# Hoja_principal_Sumo_2024.net
KiCad netlist of a schematic drawn in Altium Designer
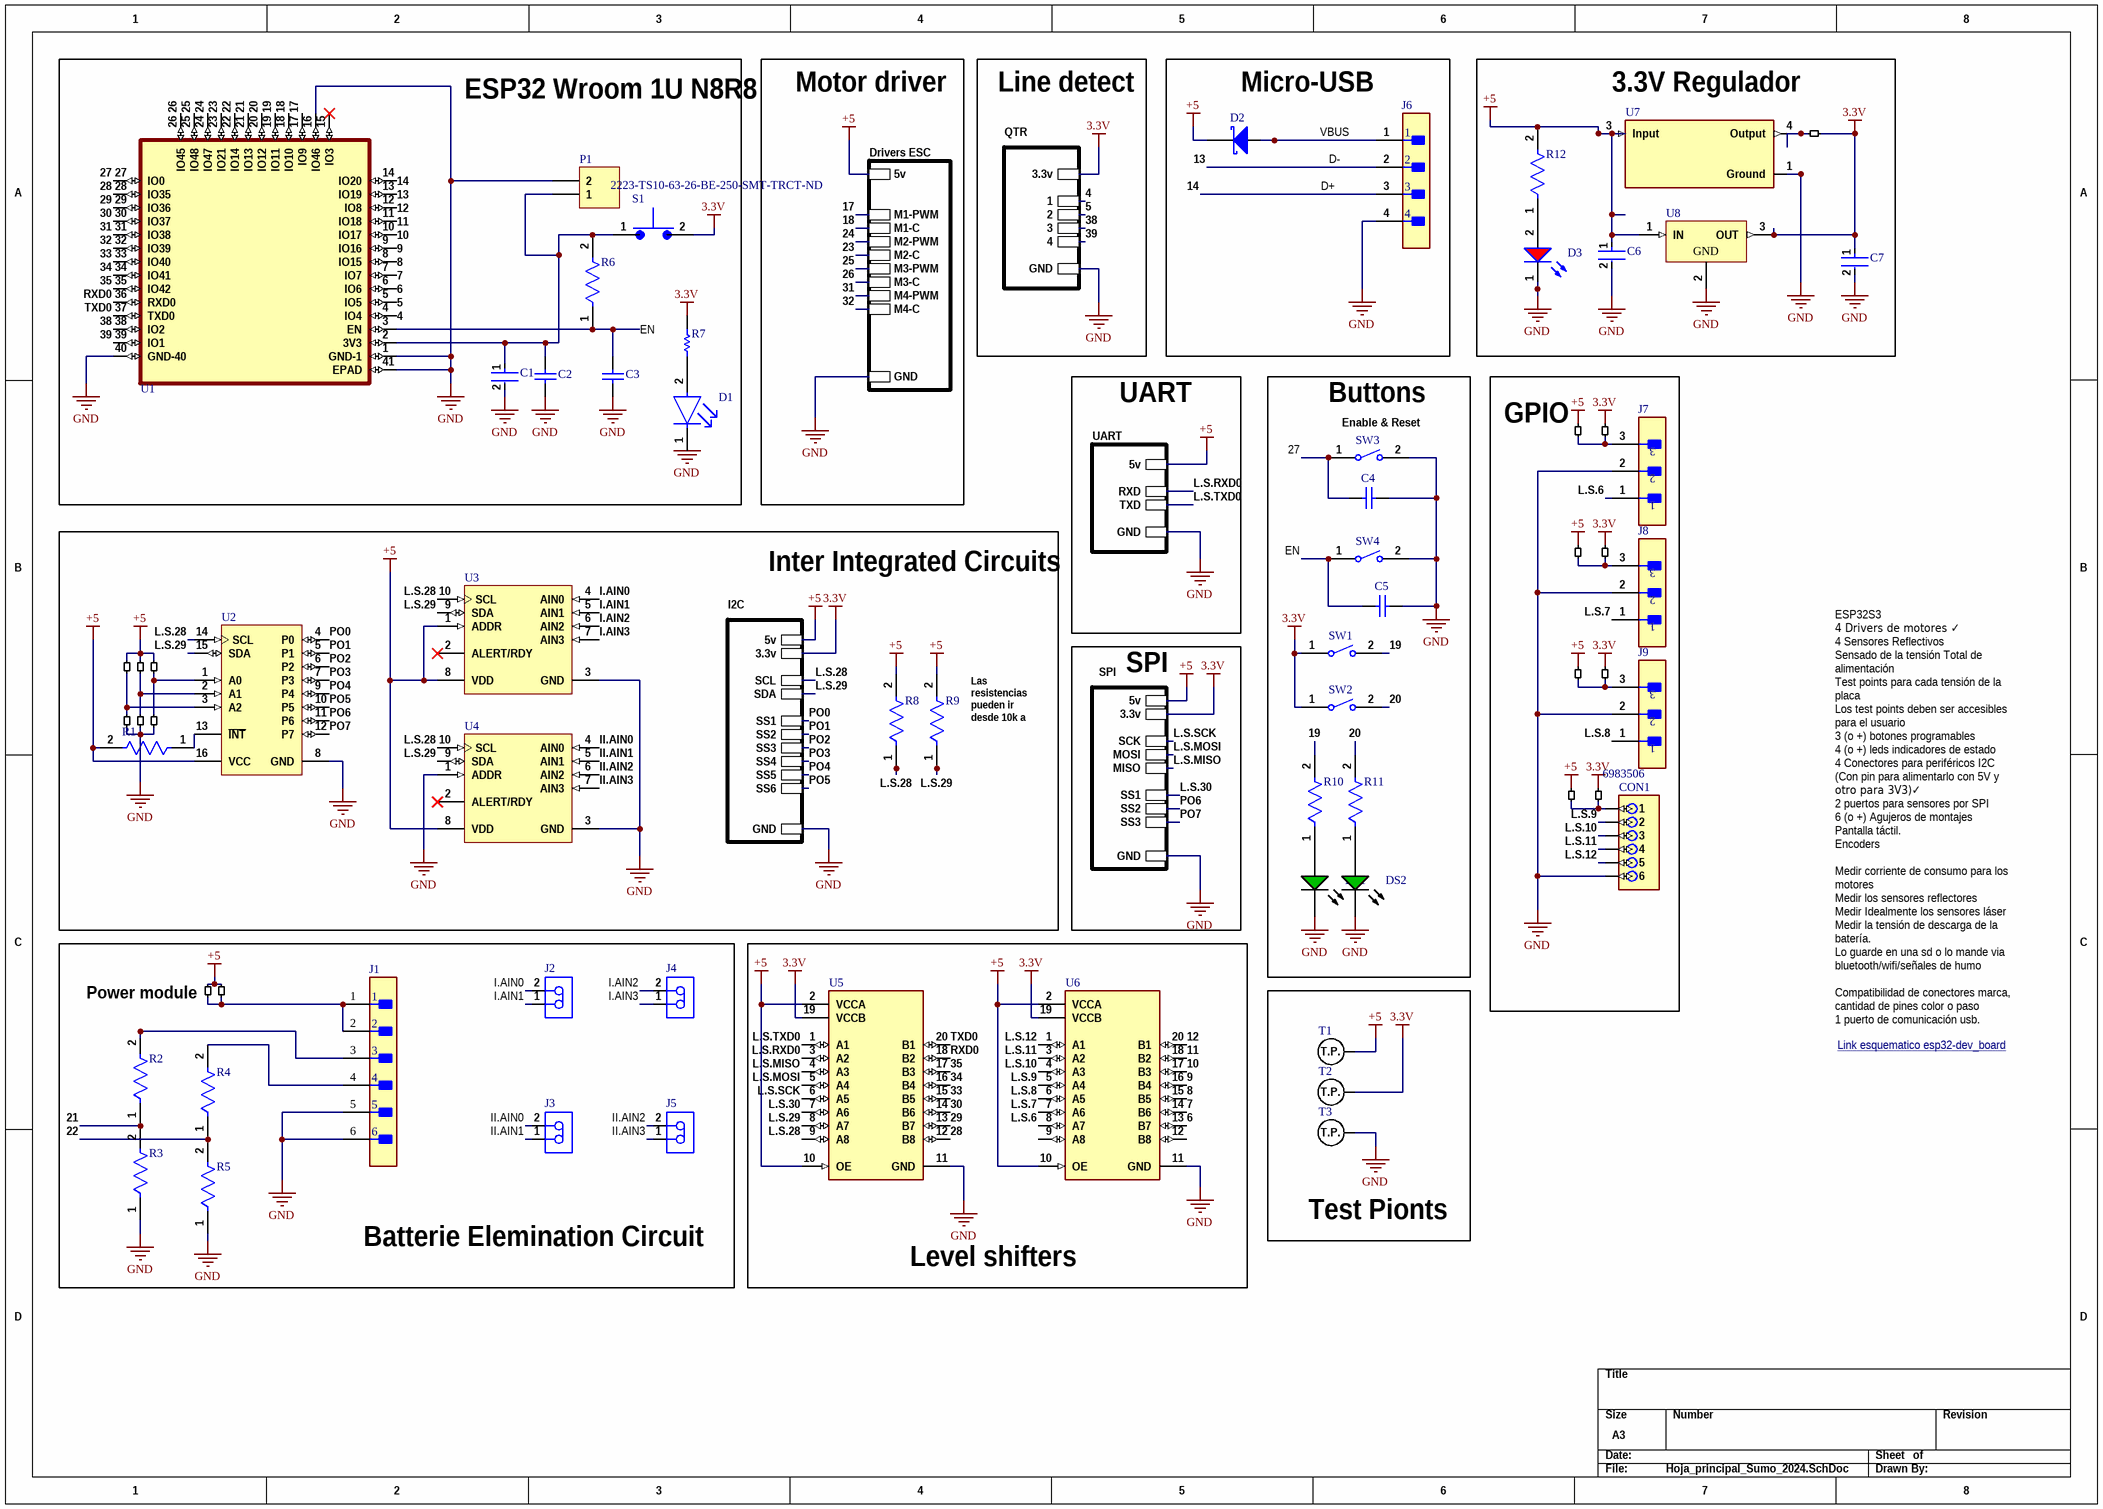
[diagram p0: Hoja_principal_Sumo_2024.SchDoc]

(export (version "E")
  (design (tool "Eeschema 10.0.6"))
  (components
    (comp (ref "C1")
      (value "TMK212BBJ106KG-T")
      (footprint "FP-0805-L_2_0_0_2-W_1_25-MFG")
      (description "Multilayer Ceramic Capacitor 10uF 25V X5R 10% SMD 0805 T/R")
      (fields (field (name "VOLTAGE") "16V") (field (name "TOLERANCE") "10%"))
      (libsource (lib "Altium Content Vault") (part "02cd4be3c70576c341d710602a673aa"))
    )
    (comp (ref "C2")
      (value "GRM21BR71H104KA01L")
      (footprint "CAPC2013X135X45ML10T25")
      (description "Chip Capacitor, 0.1 uF, +/- 10%, 50 V, -55 to 125 degC, 0805 (2012 Metric), RoHS, Tape and Reel")
      (fields (field (name "VOLTAGE") "50V") (field (name "TOLERANCE") "10%"))
      (libsource (lib "Altium Content Vault") (part "CAP-NP-2"))
    )
    (comp (ref "C3")
      (value "C0805C105K4PACTU")
      (footprint "CAPC2013X145X50LL20T25")
      (fields (field (name "MANUFACTURER") "Kemet"))
      (libsource (lib "Altium Content Vault") (part "CAP"))
    )
    (comp (ref "C4")
      (value "GRM21BR71H104KA01L")
      (footprint "CAPC2013X135X45ML10T25")
      (description "Chip Capacitor, 0.1 uF, +/- 10%, 50 V, -55 to 125 degC, 0805 (2012 Metric), RoHS, Tape and Reel")
      (fields (field (name "VOLTAGE") "50V") (field (name "TOLERANCE") "10%"))
      (libsource (lib "Altium Content Vault") (part "CAP-NP-2"))
    )
    (comp (ref "C5")
      (value "GRM21BR71H104KA01L")
      (footprint "CAPC2013X135X45ML10T25")
      (description "Chip Capacitor, 0.1 uF, +/- 10%, 50 V, -55 to 125 degC, 0805 (2012 Metric), RoHS, Tape and Reel")
      (fields (field (name "VOLTAGE") "50V") (field (name "TOLERANCE") "10%"))
      (libsource (lib "Altium Content Vault") (part "CAP-NP-2"))
    )
    (comp (ref "C6")
      (value "GRM31CR71A226KE15L")
      (footprint "FP-GRM31C-0_2-e0_3_0_8-MFG")
      (description "Chip Multilayer Ceramic Capacitors for General Purpose, 1206, 22uF, X7R, 15%, 10%, 10V")
      (fields (field (name "VOLTAGE") "10V") (field (name "TOLERANCE") "10%"))
      (libsource (lib "Altium Content Vault") (part "02cd4be3c70576c341d710602a673aa"))
    )
    (comp (ref "C7")
      (value "GRM31CR71A226KE15L")
      (footprint "FP-GRM31C-0_2-e0_3_0_8-MFG")
      (description "Chip Multilayer Ceramic Capacitors for General Purpose, 1206, 22uF, X7R, 15%, 10%, 10V")
      (fields (field (name "VOLTAGE") "10V") (field (name "TOLERANCE") "10%"))
      (libsource (lib "Altium Content Vault") (part "02cd4be3c70576c341d710602a673aa"))
    )
    (comp (ref "CON1")
      (value "B6B-ZR")
      (footprint "B6B-ZR")
      (description "Connector Header Surface Mount 6 position 0.059 (1.50mm)")
      (fields (field (name "MF") "JST") (field (name "SUPPLIER PART NUMBER 1") "6983506"))
      (libsource (lib "B6B-ZR") (part "B6B-ZR"))
    )
    (comp (ref "D1")
      (value "APHCM2012SYCK-F01")
      (footprint "FP-APHCM2012SYCK-F01-MFG")
      (description "LED YELLOW CLEAR CHIP SMD")
      (libsource (lib "Altium Content Vault") (part "8706943c75ba83719d021d2fdc84c58"))
    )
    (comp (ref "D2")
      (value "BAS3010A03WE6327HTSA1")
      (footprint "INF-SOD323_V")
      (description "Medium Power AF Schottky Diode, 0.41 V, 1 A, -65 to 125 degC, 2-Pin SOD323, RoHS, Tape and Reel")
      (fields (field (name "MANUFACTURER") "Infineon"))
      (libsource (lib "Altium Content Vault") (part "DSKY-KA-2"))
    )
    (comp (ref "D3")
      (value "150080SS75000")
      (footprint "WL-SMCW_0805_150080xx75000")
      (libsource (lib "Altium Content Vault") (part "LED_Red_2A-1K"))
    )
    (comp (ref "DS1")
      (value "HSMG-C170")
      (footprint "AVAG-HSMX-C170_V")
      (description "Chip LED, Green, 2.2 V, -40 to 85 degC, 2-Pin SMD, Pb-Free, Tape and Reel")
      (fields (field (name "MANUFACTURER") "Avago"))
      (libsource (lib "Altium Content Vault") (part "LED_GREEN_A1K2-2"))
    )
    (comp (ref "DS2")
      (value "HSMG-C170")
      (footprint "AVAG-HSMX-C170_V")
      (description "Chip LED, Green, 2.2 V, -40 to 85 degC, 2-Pin SMD, Pb-Free, Tape and Reel")
      (fields (field (name "MANUFACTURER") "Avago"))
      (libsource (lib "Altium Content Vault") (part "LED_GREEN_A1K2-2"))
    )
    (comp (ref "J1")
      (value "B6B-PH-K-K(LF)(SN)")
      (footprint "FP-B6B-PH-K-K_LF_SN-MFG")
      (description "PH Series 6 Position 2 mm Pitch Through Hole Top Entry Shrouded Header")
      (libsource (lib "Altium Content Vault") (part "f2cb566baf1c37ab5a3b8e90bbeafd6"))
    )
    (comp (ref "J2")
      (value "B2B-PH-K-S(LF)(SN)")
      (footprint "JST-B2B-PH-K-S_V")
      (fields (field (name "MANUFACTURER") "JST"))
      (libsource (lib "Altium Content Vault") (part "CN-2P-F-QF2"))
    )
    (comp (ref "J3")
      (value "B2B-PH-K-S(LF)(SN)")
      (footprint "JST-B2B-PH-K-S_V")
      (fields (field (name "MANUFACTURER") "JST"))
      (libsource (lib "Altium Content Vault") (part "CN-2P-F-QF2"))
    )
    (comp (ref "J4")
      (value "B2B-PH-K-S(LF)(SN)")
      (footprint "JST-B2B-PH-K-S_V")
      (fields (field (name "MANUFACTURER") "JST"))
      (libsource (lib "Altium Content Vault") (part "CN-2P-F-QF2"))
    )
    (comp (ref "J5")
      (value "B2B-PH-K-S(LF)(SN)")
      (footprint "JST-B2B-PH-K-S_V")
      (fields (field (name "MANUFACTURER") "JST"))
      (libsource (lib "Altium Content Vault") (part "CN-2P-F-QF2"))
    )
    (comp (ref "J6")
      (value "B4B-ZR(LF)(SN)")
      (footprint "FP-B4B-ZR_LF_SN-MFG")
      (description "CONN HEADER VERT 4POS 1.5MM")
      (libsource (lib "Altium Content Vault") (part "299a8cea1bdcbc3624fe62c390fa72c"))
    )
    (comp (ref "J7")
      (value "B3B-ZR(LF)(SN)")
      (footprint "FP-B3B-ZR_LF_SN-MFG")
      (description "CONN HEADER VERT 3POS 1.5MM")
      (libsource (lib "Altium Content Vault") (part "0d3f023dd272f625e17a2be33dea85f"))
    )
    (comp (ref "J8")
      (value "B3B-ZR(LF)(SN)")
      (footprint "FP-B3B-ZR_LF_SN-MFG")
      (description "CONN HEADER VERT 3POS 1.5MM")
      (libsource (lib "Altium Content Vault") (part "0d3f023dd272f625e17a2be33dea85f"))
    )
    (comp (ref "J9")
      (value "B3B-ZR(LF)(SN)")
      (footprint "FP-B3B-ZR_LF_SN-MFG")
      (description "CONN HEADER VERT 3POS 1.5MM")
      (libsource (lib "Altium Content Vault") (part "0d3f023dd272f625e17a2be33dea85f"))
    )
    (comp (ref "P1")
      (value "Header 2")
      (footprint "HDR1X2")
      (description "Header, 2-Pin")
      (fields (field (name "PUBLISHER") "Altium Limited"))
      (libsource (lib "Miscellaneous Connectors") (part "Header 2"))
    )
    (comp (ref "R1")
      (value "CRCW080510K0FKEA")
      (footprint "FP-CRCW0805-e3-IPC_A")
      (description "RES Thick Film, 10kΩ, 1%, 0.125W, 100ppm/°C, 0805")
      (fields (field (name "TOLERANCE") "1%"))
      (libsource (lib "Altium Content Vault") (part "1029c3af85768c4190bb7ad29bc67b5"))
    )
    (comp (ref "R2")
      (value "RC0805FR-07100KL")
      (footprint "FP-RC0805-0_6-IPC_C")
      (description "RES 100K OHM 1% 1/8W 0805")
      (fields (field (name "TOLERANCE") "1%"))
      (libsource (lib "Altium Content Vault") (part "1029c3af85768c4190bb7ad29bc67b5"))
    )
    (comp (ref "R3")
      (value "CRCW080547K0FKEA")
      (footprint "FP-CRCW0805-e3-MFG")
      (description "RES Thick Film, 47kΩ, 1%, 0.125W, 100ppm/°C, 0805")
      (fields (field (name "TOLERANCE") "1%"))
      (libsource (lib "Altium Content Vault") (part "1029c3af85768c4190bb7ad29bc67b5"))
    )
    (comp (ref "R4")
      (value "RC0805FR-07100KL")
      (footprint "FP-RC0805-0_6-IPC_C")
      (description "RES 100K OHM 1% 1/8W 0805")
      (fields (field (name "TOLERANCE") "1%"))
      (libsource (lib "Altium Content Vault") (part "1029c3af85768c4190bb7ad29bc67b5"))
    )
    (comp (ref "R5")
      (value "CRCW080547K0FKEA")
      (footprint "FP-CRCW0805-e3-MFG")
      (description "RES Thick Film, 47kΩ, 1%, 0.125W, 100ppm/°C, 0805")
      (fields (field (name "TOLERANCE") "1%"))
      (libsource (lib "Altium Content Vault") (part "1029c3af85768c4190bb7ad29bc67b5"))
    )
    (comp (ref "R6")
      (value "CRCW080510K0FKEA")
      (footprint "FP-CRCW0805-e3-IPC_A")
      (description "RES Thick Film, 10kΩ, 1%, 0.125W, 100ppm/°C, 0805")
      (fields (field (name "TOLERANCE") "1%"))
      (libsource (lib "Altium Content Vault") (part "1029c3af85768c4190bb7ad29bc67b5"))
    )
    (comp (ref "R7")
      (value "CRCW0805680RFKEA")
      (footprint "RESC2013X50X30NL20T20")
      (fields (field (name "MANUFACTURER") "Vishay Dale"))
      (libsource (lib "Altium Content Vault") (part "RES"))
    )
    (comp (ref "R8")
      (value "CRCW080510K0FKEA")
      (footprint "FP-CRCW0805-e3-IPC_A")
      (description "RES Thick Film, 10kΩ, 1%, 0.125W, 100ppm/°C, 0805")
      (fields (field (name "TOLERANCE") "1%"))
      (libsource (lib "Altium Content Vault") (part "1029c3af85768c4190bb7ad29bc67b5"))
    )
    (comp (ref "R9")
      (value "CRCW080510K0FKEA")
      (footprint "FP-CRCW0805-e3-IPC_A")
      (description "RES Thick Film, 10kΩ, 1%, 0.125W, 100ppm/°C, 0805")
      (fields (field (name "TOLERANCE") "1%"))
      (libsource (lib "Altium Content Vault") (part "1029c3af85768c4190bb7ad29bc67b5"))
    )
    (comp (ref "R10")
      (value "CRCW0805390RFKEA")
      (footprint "FP-CRCW0805-e3-IPC_B")
      (description "RES Thick Film, 390Ω, 1%, 0.125W, 100ppm/°C, 0805")
      (fields (field (name "TOLERANCE") "1%"))
      (libsource (lib "Altium Content Vault") (part "1029c3af85768c4190bb7ad29bc67b5"))
    )
    (comp (ref "R11")
      (value "CRCW0805390RFKEA")
      (footprint "FP-CRCW0805-e3-IPC_B")
      (description "RES Thick Film, 390Ω, 1%, 0.125W, 100ppm/°C, 0805")
      (fields (field (name "TOLERANCE") "1%"))
      (libsource (lib "Altium Content Vault") (part "1029c3af85768c4190bb7ad29bc67b5"))
    )
    (comp (ref "R12")
      (value "CRCW080510K0FKEA")
      (footprint "FP-CRCW0805-e3-IPC_A")
      (description "RES Thick Film, 10kΩ, 1%, 0.125W, 100ppm/°C, 0805")
      (fields (field (name "TOLERANCE") "1%"))
      (libsource (lib "Altium Content Vault") (part "1029c3af85768c4190bb7ad29bc67b5"))
    )
    (comp (ref "S1")
      (value "TS10-63-26-BE-250-SMT-TR")
      (footprint "SW_TS10-63-26-BE-250-SMT-TR")
      (fields (field (name "SUPPLIER PART NUMBER 1") "2223-TS10-63-26-BE-250-SMT-TRCT-ND"))
      (libsource (lib "TS10-63-26-BE-250-SMT-TR") (part "TS10-63-26-BE-250-SMT-TR"))
    )
    (comp (ref "SW1")
      (value "FSMSMTR")
      (footprint "TECO-FSMSMTR_V")
      (description "FSMSM Push Button Switch, 50 mA, -35 to 85 degC, 2-Pin SMD, RoHS, Tape and Reel")
      (fields (field (name "MANUFACTURER") "TE Connectivity"))
      (libsource (lib "Altium Content Vault") (part "SW-SPST-2_C"))
    )
    (comp (ref "SW2")
      (value "FSMSMTR")
      (footprint "TECO-FSMSMTR_V")
      (description "FSMSM Push Button Switch, 50 mA, -35 to 85 degC, 2-Pin SMD, RoHS, Tape and Reel")
      (fields (field (name "MANUFACTURER") "TE Connectivity"))
      (libsource (lib "Altium Content Vault") (part "SW-SPST-2_C"))
    )
    (comp (ref "SW3")
      (value "FSMSMTR")
      (footprint "TECO-FSMSMTR_V")
      (description "FSMSM Push Button Switch, 50 mA, -35 to 85 degC, 2-Pin SMD, RoHS, Tape and Reel")
      (fields (field (name "MANUFACTURER") "TE Connectivity"))
      (libsource (lib "Altium Content Vault") (part "SW-SPST-2_C"))
    )
    (comp (ref "SW4")
      (value "FSMSMTR")
      (footprint "TECO-FSMSMTR_V")
      (description "FSMSM Push Button Switch, 50 mA, -35 to 85 degC, 2-Pin SMD, RoHS, Tape and Reel")
      (fields (field (name "MANUFACTURER") "TE Connectivity"))
      (libsource (lib "Altium Content Vault") (part "SW-SPST-2_C"))
    )
    (comp (ref "T1")
      (value "Test point")
      (footprint "Testpoint")
      (libsource (lib "Schlib2") (part "Test point"))
    )
    (comp (ref "T2")
      (value "Test point")
      (footprint "Testpoint")
      (libsource (lib "Schlib2") (part "Test point"))
    )
    (comp (ref "T3")
      (value "Test point")
      (footprint "Testpoint")
      (libsource (lib "Schlib2") (part "Test point"))
    )
    (comp (ref "U1")
      (value "ESP32-S3-WROOM-1 N8R8")
      (footprint "PCBComponent_1")
      (description "SMD MODULE, ESP32-S3R8 WITH 8 MB")
      (fields (field (name "MF") "Espressif Systems") (field (name "MP") "ESP32-S3-WROOM-1"))
      (libsource (lib "ESP32-S3-WROOM-1") (part "ESP32-S3-WROOM-1"))
    )
    (comp (ref "U2")
      (value "PCF8574DWR")
      (footprint "DW0016A_L")
      (fields (field (name "MANUFACTURER") "Texas Instruments"))
      (libsource (lib "Altium Content Vault") (part "TI-PCF8574-SOIC_DW-16"))
    )
    (comp (ref "U3")
      (value "ADS1115IDGST")
      (footprint "TI-DGS10_N")
      (fields (field (name "MANUFACTURER") "Texas Instruments"))
      (libsource (lib "Altium Content Vault") (part "TI-ADS1015_1115-10"))
    )
    (comp (ref "U4")
      (value "ADS1115IDGST")
      (footprint "TI-DGS10_N")
      (fields (field (name "MANUFACTURER") "Texas Instruments"))
      (libsource (lib "Altium Content Vault") (part "TI-ADS1015_1115-10"))
    )
    (comp (ref "U5")
      (value "TXS0108EQPWRQ1")
      (footprint "FP-PW0020A-MFG")
      (description "IC TRNSLTR BIDIRECTIONAL 20TSSOP")
      (fields
        (field (name "OCTOPART") "https://octopart.com/txs0108eqpwrq1-texas+instruments-59160487")
        (field (name "MANUFACTURER") "Texas Instruments")
      )
      (libsource (lib "Altium Content Vault") (part "b852cf3f2c97e4a3d4172ee3f19d589"))
    )
    (comp (ref "U6")
      (value "TXS0108EQPWRQ1")
      (footprint "FP-PW0020A-MFG")
      (description "IC TRNSLTR BIDIRECTIONAL 20TSSOP")
      (fields
        (field (name "OCTOPART") "https://octopart.com/txs0108eqpwrq1-texas+instruments-59160487")
        (field (name "MANUFACTURER") "Texas Instruments")
      )
      (libsource (lib "Altium Content Vault") (part "b852cf3f2c97e4a3d4172ee3f19d589"))
    )
    (comp (ref "U7")
      (value "NCP1117DT33T5G")
      (footprint "FP-369C-MFG")
      (description "IC REG LINEAR 3.3V 1A DPAK")
      (libsource (lib "Altium Content Vault") (part "f1512ae604efdd4bd306cab1b45f420"))
    )
    (comp (ref "U8")
      (value "3.3v")
      (footprint "FAIR-TO-220-3")
      (description "Positive Voltage Regulator, 5 V, 1 A, -40 to 125 degC, 3-Pin TO-220, RoHS, Tube")
      (fields (field (name "MANUFACTURER") "FairchildSemiconductor"))
      (libsource (lib "Altium Content Vault") (part "FAIR-LM7805CT-TO220-3"))
    )
    (comp (ref "W1") (value "Jumper") (footprint "Jumper Mini") (libsource (lib "Schlib1") (part "Jumper")))
    (comp (ref "W2") (value "Jumper") (footprint "Jumper Mini") (libsource (lib "Schlib1") (part "Jumper")))
    (comp (ref "W3") (value "Jumper") (footprint "Jumper Mini") (libsource (lib "Schlib1") (part "Jumper")))
    (comp (ref "W4") (value "Jumper") (footprint "Jumper Mini") (libsource (lib "Schlib1") (part "Jumper")))
    (comp (ref "W5") (value "Jumper") (footprint "Jumper Mini") (libsource (lib "Schlib1") (part "Jumper")))
    (comp (ref "W6") (value "Jumper") (footprint "Jumper Mini") (libsource (lib "Schlib1") (part "Jumper")))
    (comp (ref "W7") (value "Jumper") (footprint "Jumper Mid") (libsource (lib "Schlib1") (part "Jumper")))
    (comp (ref "W8") (value "Jumper") (footprint "Jumper Mid") (libsource (lib "Schlib1") (part "Jumper")))
    (comp (ref "W9") (value "Jumper") (footprint "Jumper Mid") (libsource (lib "Schlib1") (part "Jumper")))
    (comp (ref "W10") (value "Jumper") (footprint "Jumper Mid") (libsource (lib "Schlib1") (part "Jumper")))
    (comp (ref "W11") (value "Jumper") (footprint "Jumper Mid") (libsource (lib "Schlib1") (part "Jumper")))
    (comp (ref "W12") (value "Jumper") (footprint "Jumper Mid") (libsource (lib "Schlib1") (part "Jumper")))
    (comp (ref "W13") (value "Jumper") (footprint "Jumper Mid") (libsource (lib "Schlib1") (part "Jumper")))
    (comp (ref "W14") (value "Jumper") (footprint "Jumper Mid") (libsource (lib "Schlib1") (part "Jumper")))
    (comp (ref "W15") (value "Jumper") (footprint "Jumper Mid") (libsource (lib "Schlib1") (part "Jumper")))
    (comp (ref "W16") (value "Jumper") (footprint "Jumper Mid") (libsource (lib "Schlib1") (part "Jumper")))
    (comp (ref "W17") (value "Jumper") (footprint "Jumper Mid") (libsource (lib "Schlib1") (part "Jumper")))
  )
  (nets
    (net (code "1") (name "+5") (class "Default")
      (node (ref "C6") (pin "1") (pinfunction "1_1") (pintype "passive"))
      (node (ref "D2") (pin "1") (pinfunction "K_1") (pintype "passive"))
      (node (ref "R1") (pin "2") (pinfunction "2_2") (pintype "passive"))
      (node (ref "R12") (pin "2") (pinfunction "2_2") (pintype "passive"))
      (node (ref "R8") (pin "2") (pinfunction "2_2") (pintype "passive"))
      (node (ref "R9") (pin "2") (pinfunction "2_2") (pintype "passive"))
      (node (ref "T1") (pin "1") (pinfunction "T.P._1") (pintype "passive"))
      (node (ref "U2") (pin "16") (pinfunction "VCC_16") (pintype "power_in"))
      (node (ref "U3") (pin "1") (pinfunction "ADDR_1") (pintype "input"))
      (node (ref "U3") (pin "8") (pinfunction "VDD_8") (pintype "power_in"))
      (node (ref "U4") (pin "8") (pinfunction "VDD_8") (pintype "power_in"))
      (node (ref "U5") (pin "10") (pinfunction "OE_10") (pintype "input"))
      (node (ref "U5") (pin "2") (pinfunction "VCCA_2") (pintype "power_in"))
      (node (ref "U6") (pin "10") (pinfunction "OE_10") (pintype "input"))
      (node (ref "U6") (pin "2") (pinfunction "VCCA_2") (pintype "power_in"))
      (node (ref "U7") (pin "3") (pinfunction "Input_3") (pintype "input"))
      (node (ref "U8") (pin "1") (pinfunction "IN_1") (pintype "input"))
      (node (ref "W1") (pin "2") (pinfunction "2_2") (pintype "passive"))
      (node (ref "W10") (pin "2") (pinfunction "2_2") (pintype "passive"))
      (node (ref "W11") (pin "2") (pinfunction "2_2") (pintype "passive"))
      (node (ref "W12") (pin "2") (pinfunction "2_2") (pintype "passive"))
      (node (ref "W3") (pin "2") (pinfunction "2_2") (pintype "passive"))
      (node (ref "W5") (pin "2") (pinfunction "2_2") (pintype "passive"))
      (node (ref "W7") (pin "2") (pinfunction "2_2") (pintype "passive"))
      (node (ref "W8") (pin "2") (pinfunction "2_2") (pintype "passive"))
      (node (ref "W9") (pin "2") (pinfunction "2_2") (pintype "passive"))
    )
    (net (code "2") (name "/4") (class "Default")
      (node (ref "U1") (pin "4") (pinfunction "IO4_4") (pintype "bidirectional"))
    )
    (net (code "3") (name "/5") (class "Default")
      (node (ref "U1") (pin "5") (pinfunction "IO5_5") (pintype "bidirectional"))
    )
    (net (code "4") (name "/6") (class "Default")
      (node (ref "U1") (pin "6") (pinfunction "IO6_6") (pintype "bidirectional"))
      (node (ref "U6") (pin "13") (pinfunction "B7_13") (pintype "bidirectional"))
    )
    (net (code "5") (name "/7") (class "Default")
      (node (ref "U1") (pin "7") (pinfunction "IO7_7") (pintype "bidirectional"))
      (node (ref "U6") (pin "14") (pinfunction "B6_14") (pintype "bidirectional"))
    )
    (net (code "6") (name "/8") (class "Default")
      (node (ref "U1") (pin "8") (pinfunction "IO15_8") (pintype "bidirectional"))
      (node (ref "U6") (pin "15") (pinfunction "B5_15") (pintype "bidirectional"))
    )
    (net (code "7") (name "/9") (class "Default")
      (node (ref "U1") (pin "9") (pinfunction "IO16_9") (pintype "bidirectional"))
      (node (ref "U6") (pin "16") (pinfunction "B4_16") (pintype "bidirectional"))
    )
    (net (code "8") (name "/10") (class "Default")
      (node (ref "U1") (pin "10") (pinfunction "IO17_10") (pintype "bidirectional"))
      (node (ref "U6") (pin "17") (pinfunction "B3_17") (pintype "bidirectional"))
    )
    (net (code "9") (name "/11") (class "Default")
      (node (ref "U1") (pin "11") (pinfunction "IO18_11") (pintype "bidirectional"))
      (node (ref "U6") (pin "18") (pinfunction "B2_18") (pintype "bidirectional"))
    )
    (net (code "10") (name "/12") (class "Default")
      (node (ref "U1") (pin "12") (pinfunction "IO8_12") (pintype "bidirectional"))
      (node (ref "U6") (pin "20") (pinfunction "B1_20") (pintype "bidirectional"))
    )
    (net (code "11") (name "/13") (class "Default")
      (node (ref "J6") (pin "2") (pinfunction "2_2") (pintype "passive"))
      (node (ref "U1") (pin "13") (pinfunction "IO19_13") (pintype "bidirectional"))
    )
    (net (code "12") (name "/14") (class "Default")
      (node (ref "J6") (pin "3") (pinfunction "3_3") (pintype "passive"))
      (node (ref "U1") (pin "14") (pinfunction "IO20_14") (pintype "bidirectional"))
    )
    (net (code "13") (name "/17") (class "Default")
      (node (ref "U1") (pin "17") (pinfunction "IO9_17") (pintype "bidirectional"))
    )
    (net (code "14") (name "/18") (class "Default")
      (node (ref "U1") (pin "18") (pinfunction "IO10_18") (pintype "bidirectional"))
    )
    (net (code "15") (name "/19") (class "Default")
      (node (ref "R10") (pin "2") (pinfunction "2_2") (pintype "passive"))
      (node (ref "SW1") (pin "2") (pinfunction "2_2") (pintype "passive"))
      (node (ref "U1") (pin "19") (pinfunction "IO11_19") (pintype "bidirectional"))
    )
    (net (code "16") (name "/20") (class "Default")
      (node (ref "R11") (pin "2") (pinfunction "2_2") (pintype "passive"))
      (node (ref "SW2") (pin "2") (pinfunction "2_2") (pintype "passive"))
      (node (ref "U1") (pin "20") (pinfunction "IO12_20") (pintype "bidirectional"))
    )
    (net (code "17") (name "/21") (class "Default")
      (node (ref "R2") (pin "1") (pinfunction "1_1") (pintype "passive"))
      (node (ref "R3") (pin "2") (pinfunction "2_2") (pintype "passive"))
      (node (ref "U1") (pin "21") (pinfunction "IO13_21") (pintype "bidirectional"))
    )
    (net (code "18") (name "/22") (class "Default")
      (node (ref "R4") (pin "1") (pinfunction "1_1") (pintype "passive"))
      (node (ref "R5") (pin "2") (pinfunction "2_2") (pintype "passive"))
      (node (ref "U1") (pin "22") (pinfunction "IO14_22") (pintype "bidirectional"))
    )
    (net (code "19") (name "/23") (class "Default")
      (node (ref "U1") (pin "23") (pinfunction "IO21_23") (pintype "bidirectional"))
    )
    (net (code "20") (name "/24") (class "Default")
      (node (ref "U1") (pin "24") (pinfunction "IO47_24") (pintype "bidirectional"))
    )
    (net (code "21") (name "/25") (class "Default")
      (node (ref "U1") (pin "25") (pinfunction "IO48_25") (pintype "bidirectional"))
    )
    (net (code "22") (name "/26") (class "Default")
      (node (ref "U1") (pin "26") (pinfunction "IO45_26") (pintype "bidirectional"))
    )
    (net (code "23") (name "/27") (class "Default")
      (node (ref "C4") (pin "2") (pinfunction "2_2") (pintype "passive"))
      (node (ref "SW3") (pin "1") (pinfunction "1_1") (pintype "passive"))
      (node (ref "U1") (pin "27") (pinfunction "IO0_27") (pintype "bidirectional"))
    )
    (net (code "24") (name "/28") (class "Default")
      (node (ref "U1") (pin "28") (pinfunction "IO35_28") (pintype "bidirectional"))
      (node (ref "U5") (pin "12") (pinfunction "B8_12") (pintype "bidirectional"))
    )
    (net (code "25") (name "/29") (class "Default")
      (node (ref "U1") (pin "29") (pinfunction "IO36_29") (pintype "bidirectional"))
      (node (ref "U5") (pin "13") (pinfunction "B7_13") (pintype "bidirectional"))
    )
    (net (code "26") (name "/30") (class "Default")
      (node (ref "U1") (pin "30") (pinfunction "IO37_30") (pintype "bidirectional"))
      (node (ref "U5") (pin "14") (pinfunction "B6_14") (pintype "bidirectional"))
    )
    (net (code "27") (name "/31") (class "Default")
      (node (ref "U1") (pin "31") (pinfunction "IO38_31") (pintype "bidirectional"))
    )
    (net (code "28") (name "/32") (class "Default")
      (node (ref "U1") (pin "32") (pinfunction "IO39_32") (pintype "bidirectional"))
    )
    (net (code "29") (name "/33") (class "Default")
      (node (ref "U1") (pin "33") (pinfunction "IO40_33") (pintype "bidirectional"))
      (node (ref "U5") (pin "15") (pinfunction "B5_15") (pintype "bidirectional"))
    )
    (net (code "30") (name "/34") (class "Default")
      (node (ref "U1") (pin "34") (pinfunction "IO41_34") (pintype "bidirectional"))
      (node (ref "U5") (pin "16") (pinfunction "B4_16") (pintype "bidirectional"))
    )
    (net (code "31") (name "/35") (class "Default")
      (node (ref "U1") (pin "35") (pinfunction "IO42_35") (pintype "bidirectional"))
      (node (ref "U5") (pin "17") (pinfunction "B3_17") (pintype "bidirectional"))
    )
    (net (code "32") (name "/38") (class "Default")
      (node (ref "U1") (pin "38") (pinfunction "IO2_38") (pintype "bidirectional"))
    )
    (net (code "33") (name "/39") (class "Default")
      (node (ref "U1") (pin "39") (pinfunction "IO1_39") (pintype "bidirectional"))
    )
    (net (code "34") (name "/EN") (class "Default")
      (node (ref "C3") (pin "2") (pinfunction "2_2") (pintype "passive"))
      (node (ref "C5") (pin "2") (pinfunction "2_2") (pintype "passive"))
      (node (ref "R6") (pin "1") (pinfunction "1_1") (pintype "passive"))
      (node (ref "SW4") (pin "1") (pinfunction "1_1") (pintype "passive"))
      (node (ref "U1") (pin "3") (pinfunction "EN_3") (pintype "bidirectional"))
    )
    (net (code "35") (name "/I.AIN0") (class "Default")
      (node (ref "J2") (pin "2") (pinfunction "2_2") (pintype "passive"))
      (node (ref "U3") (pin "4") (pinfunction "AIN0_4") (pintype "input"))
    )
    (net (code "36") (name "/I.AIN1") (class "Default")
      (node (ref "J2") (pin "1") (pinfunction "1_1") (pintype "passive"))
      (node (ref "U3") (pin "5") (pinfunction "AIN1_5") (pintype "input"))
    )
    (net (code "37") (name "/I.AIN2") (class "Default")
      (node (ref "J4") (pin "2") (pinfunction "2_2") (pintype "passive"))
      (node (ref "U3") (pin "6") (pinfunction "AIN2_6") (pintype "input"))
    )
    (net (code "38") (name "/I.AIN3") (class "Default")
      (node (ref "J4") (pin "1") (pinfunction "1_1") (pintype "passive"))
      (node (ref "U3") (pin "7") (pinfunction "AIN3_7") (pintype "input"))
    )
    (net (code "39") (name "/II.AIN0") (class "Default")
      (node (ref "J3") (pin "2") (pinfunction "2_2") (pintype "passive"))
      (node (ref "U4") (pin "4") (pinfunction "AIN0_4") (pintype "input"))
    )
    (net (code "40") (name "/II.AIN1") (class "Default")
      (node (ref "J3") (pin "1") (pinfunction "1_1") (pintype "passive"))
      (node (ref "U4") (pin "5") (pinfunction "AIN1_5") (pintype "input"))
    )
    (net (code "41") (name "/II.AIN2") (class "Default")
      (node (ref "J5") (pin "2") (pinfunction "2_2") (pintype "passive"))
      (node (ref "U4") (pin "6") (pinfunction "AIN2_6") (pintype "input"))
    )
    (net (code "42") (name "/II.AIN3") (class "Default")
      (node (ref "J5") (pin "1") (pinfunction "1_1") (pintype "passive"))
      (node (ref "U4") (pin "7") (pinfunction "AIN3_7") (pintype "input"))
    )
    (net (code "43") (name "/L.S.6") (class "Default")
      (node (ref "J7") (pin "1") (pinfunction "1_1") (pintype "passive"))
      (node (ref "U6") (pin "8") (pinfunction "A7_8") (pintype "bidirectional"))
    )
    (net (code "44") (name "/L.S.7") (class "Default")
      (node (ref "J8") (pin "1") (pinfunction "1_1") (pintype "passive"))
      (node (ref "U6") (pin "7") (pinfunction "A6_7") (pintype "bidirectional"))
    )
    (net (code "45") (name "/L.S.8") (class "Default")
      (node (ref "J9") (pin "1") (pinfunction "1_1") (pintype "passive"))
      (node (ref "U6") (pin "6") (pinfunction "A5_6") (pintype "bidirectional"))
    )
    (net (code "46") (name "/L.S.9") (class "Default")
      (node (ref "CON1") (pin "2") (pinfunction "2_2") (pintype "bidirectional"))
      (node (ref "U6") (pin "5") (pinfunction "A4_5") (pintype "bidirectional"))
    )
    (net (code "47") (name "/L.S.10") (class "Default")
      (node (ref "CON1") (pin "3") (pinfunction "3_3") (pintype "bidirectional"))
      (node (ref "U6") (pin "4") (pinfunction "A3_4") (pintype "bidirectional"))
    )
    (net (code "48") (name "/L.S.11") (class "Default")
      (node (ref "CON1") (pin "4") (pinfunction "4_4") (pintype "bidirectional"))
      (node (ref "U6") (pin "3") (pinfunction "A2_3") (pintype "bidirectional"))
    )
    (net (code "49") (name "/L.S.12") (class "Default")
      (node (ref "CON1") (pin "5") (pinfunction "5_5") (pintype "bidirectional"))
      (node (ref "U6") (pin "1") (pinfunction "A1_1") (pintype "bidirectional"))
    )
    (net (code "50") (name "/L.S.28") (class "Default")
      (node (ref "R8") (pin "1") (pinfunction "1_1") (pintype "passive"))
      (node (ref "U2") (pin "14") (pinfunction "SCL_14") (pintype "input"))
      (node (ref "U3") (pin "10") (pinfunction "SCL_10") (pintype "input"))
      (node (ref "U4") (pin "10") (pinfunction "SCL_10") (pintype "input"))
      (node (ref "U5") (pin "9") (pinfunction "A8_9") (pintype "bidirectional"))
    )
    (net (code "51") (name "/L.S.29") (class "Default")
      (node (ref "R9") (pin "1") (pinfunction "1_1") (pintype "passive"))
      (node (ref "U2") (pin "15") (pinfunction "SDA_15") (pintype "bidirectional"))
      (node (ref "U3") (pin "9") (pinfunction "SDA_9") (pintype "bidirectional"))
      (node (ref "U4") (pin "9") (pinfunction "SDA_9") (pintype "bidirectional"))
      (node (ref "U5") (pin "8") (pinfunction "A7_8") (pintype "bidirectional"))
    )
    (net (code "52") (name "/L.S.30") (class "Default")
      (node (ref "U5") (pin "7") (pinfunction "A6_7") (pintype "bidirectional"))
    )
    (net (code "53") (name "/L.S.MISO") (class "Default")
      (node (ref "U5") (pin "4") (pinfunction "A3_4") (pintype "bidirectional"))
    )
    (net (code "54") (name "/L.S.MOSI") (class "Default")
      (node (ref "U5") (pin "5") (pinfunction "A4_5") (pintype "bidirectional"))
    )
    (net (code "55") (name "/L.S.RXD0") (class "Default")
      (node (ref "U5") (pin "3") (pinfunction "A2_3") (pintype "bidirectional"))
    )
    (net (code "56") (name "/L.S.SCK") (class "Default")
      (node (ref "U5") (pin "6") (pinfunction "A5_6") (pintype "bidirectional"))
    )
    (net (code "57") (name "/L.S.TXD0") (class "Default")
      (node (ref "U5") (pin "1") (pinfunction "A1_1") (pintype "bidirectional"))
    )
    (net (code "58") (name "/PO0") (class "Default")
      (node (ref "U2") (pin "4") (pinfunction "P0_4") (pintype "bidirectional"))
    )
    (net (code "59") (name "/PO1") (class "Default")
      (node (ref "U2") (pin "5") (pinfunction "P1_5") (pintype "bidirectional"))
    )
    (net (code "60") (name "/PO2") (class "Default")
      (node (ref "U2") (pin "6") (pinfunction "P2_6") (pintype "bidirectional"))
    )
    (net (code "61") (name "/PO3") (class "Default")
      (node (ref "U2") (pin "7") (pinfunction "P3_7") (pintype "bidirectional"))
    )
    (net (code "62") (name "/PO4") (class "Default")
      (node (ref "U2") (pin "9") (pinfunction "P4_9") (pintype "bidirectional"))
    )
    (net (code "63") (name "/PO5") (class "Default")
      (node (ref "U2") (pin "10") (pinfunction "P5_10") (pintype "bidirectional"))
    )
    (net (code "64") (name "/PO6") (class "Default")
      (node (ref "U2") (pin "11") (pinfunction "P6_11") (pintype "bidirectional"))
    )
    (net (code "65") (name "/PO7") (class "Default")
      (node (ref "U2") (pin "12") (pinfunction "P7_12") (pintype "bidirectional"))
    )
    (net (code "66") (name "/RXD0") (class "Default")
      (node (ref "U1") (pin "36") (pinfunction "RXD0_36") (pintype "bidirectional"))
      (node (ref "U5") (pin "18") (pinfunction "B2_18") (pintype "bidirectional"))
    )
    (net (code "67") (name "/TXD0") (class "Default")
      (node (ref "U1") (pin "37") (pinfunction "TXD0_37") (pintype "bidirectional"))
      (node (ref "U5") (pin "20") (pinfunction "B1_20") (pintype "bidirectional"))
    )
    (net (code "68") (name "/VBUS") (class "Default")
      (node (ref "D2") (pin "2") (pinfunction "A_2") (pintype "passive"))
      (node (ref "J6") (pin "1") (pinfunction "1_1") (pintype "passive"))
    )
    (net (code "69") (name "3.3V") (class "Default")
      (node (ref "C7") (pin "1") (pinfunction "1_1") (pintype "passive"))
      (node (ref "R7") (pin "2") (pinfunction "2_2") (pintype "passive"))
      (node (ref "S1") (pin "2") (pinfunction "2_2") (pintype "passive"))
      (node (ref "SW1") (pin "1") (pinfunction "1_1") (pintype "passive"))
      (node (ref "SW2") (pin "1") (pinfunction "1_1") (pintype "passive"))
      (node (ref "T2") (pin "1") (pinfunction "T.P._1") (pintype "passive"))
      (node (ref "U5") (pin "19") (pinfunction "VCCB_19") (pintype "power_in"))
      (node (ref "U6") (pin "19") (pinfunction "VCCB_19") (pintype "power_in"))
      (node (ref "U8") (pin "3") (pinfunction "OUT_3") (pintype "output"))
      (node (ref "W13") (pin "2") (pinfunction "2_2") (pintype "passive"))
      (node (ref "W14") (pin "2") (pinfunction "2_2") (pintype "passive"))
      (node (ref "W15") (pin "2") (pinfunction "2_2") (pintype "passive"))
      (node (ref "W16") (pin "2") (pinfunction "2_2") (pintype "passive"))
      (node (ref "W17") (pin "1") (pinfunction "1_1") (pintype "passive"))
    )
    (net (code "70") (name "GND") (class "Default")
      (node (ref "C1") (pin "2") (pinfunction "2_2") (pintype "passive"))
      (node (ref "C2") (pin "2") (pinfunction "2_2") (pintype "passive"))
      (node (ref "C3") (pin "1") (pinfunction "1_1") (pintype "passive"))
      (node (ref "C4") (pin "1") (pinfunction "1_1") (pintype "passive"))
      (node (ref "C5") (pin "1") (pinfunction "1_1") (pintype "passive"))
      (node (ref "C6") (pin "2") (pinfunction "2_2") (pintype "passive"))
      (node (ref "C7") (pin "2") (pinfunction "2_2") (pintype "passive"))
      (node (ref "CON1") (pin "6") (pinfunction "6_6") (pintype "bidirectional"))
      (node (ref "D3") (pin "1") (pinfunction "K_1") (pintype "passive"))
      (node (ref "DS1") (pin "2") (pinfunction "K_2") (pintype "passive"))
      (node (ref "DS2") (pin "2") (pinfunction "K_2") (pintype "passive"))
      (node (ref "J1") (pin "5") (pinfunction "5_5") (pintype "passive"))
      (node (ref "J1") (pin "6") (pinfunction "6_6") (pintype "passive"))
      (node (ref "J6") (pin "4") (pinfunction "4_4") (pintype "passive"))
      (node (ref "J7") (pin "2") (pinfunction "2_2") (pintype "passive"))
      (node (ref "J8") (pin "2") (pinfunction "2_2") (pintype "passive"))
      (node (ref "J9") (pin "2") (pinfunction "2_2") (pintype "passive"))
      (node (ref "P1") (pin "2") (pinfunction "2_2") (pintype "passive"))
      (node (ref "R3") (pin "1") (pinfunction "1_1") (pintype "passive"))
      (node (ref "R5") (pin "1") (pinfunction "1_1") (pintype "passive"))
      (node (ref "SW3") (pin "2") (pinfunction "2_2") (pintype "passive"))
      (node (ref "SW4") (pin "2") (pinfunction "2_2") (pintype "passive"))
      (node (ref "T3") (pin "1") (pinfunction "T.P._1") (pintype "passive"))
      (node (ref "U1") (pin "1") (pinfunction "GND-1_1") (pintype "bidirectional"))
      (node (ref "U1") (pin "16") (pinfunction "IO46_16") (pintype "bidirectional"))
      (node (ref "U1") (pin "40") (pinfunction "GND-40_40") (pintype "bidirectional"))
      (node (ref "U1") (pin "41") (pinfunction "EPAD_41") (pintype "bidirectional"))
      (node (ref "U2") (pin "8") (pinfunction "GND_8") (pintype "power_in"))
      (node (ref "U3") (pin "3") (pinfunction "GND_3") (pintype "power_in"))
      (node (ref "U4") (pin "1") (pinfunction "ADDR_1") (pintype "input"))
      (node (ref "U4") (pin "3") (pinfunction "GND_3") (pintype "power_in"))
      (node (ref "U5") (pin "11") (pinfunction "GND_11") (pintype "power_in"))
      (node (ref "U6") (pin "11") (pinfunction "GND_11") (pintype "power_in"))
      (node (ref "U7") (pin "1") (pinfunction "Ground_1") (pintype "power_in"))
      (node (ref "U8") (pin "2") (pinfunction "GND_2") (pintype "power_in"))
      (node (ref "W2") (pin "1") (pinfunction "1_1") (pintype "passive"))
      (node (ref "W4") (pin "1") (pinfunction "1_1") (pintype "passive"))
      (node (ref "W6") (pin "1") (pinfunction "1_1") (pintype "passive"))
    )
    (net (code "71") (name "Net-(CON1-Pad1)") (class "Default")
      (node (ref "CON1") (pin "1") (pinfunction "1_1") (pintype "bidirectional"))
      (node (ref "W13") (pin "1") (pinfunction "1_1") (pintype "passive"))
      (node (ref "W9") (pin "1") (pinfunction "1_1") (pintype "passive"))
    )
    (net (code "72") (name "Net-(D1-A)") (class "Default")
      (node (ref "D1") (pin "2") (pinfunction "A_2") (pintype "passive"))
      (node (ref "R7") (pin "1") (pinfunction "1_1") (pintype "passive"))
    )
    (net (code "73") (name "Net-(D3-A)") (class "Default")
      (node (ref "D3") (pin "2") (pinfunction "A_2") (pintype "passive"))
      (node (ref "R12") (pin "1") (pinfunction "1_1") (pintype "passive"))
    )
    (net (code "74") (name "Net-(DS1-A)") (class "Default")
      (node (ref "DS1") (pin "1") (pinfunction "A_1") (pintype "passive"))
      (node (ref "R10") (pin "1") (pinfunction "1_1") (pintype "passive"))
    )
    (net (code "75") (name "Net-(DS2-A)") (class "Default")
      (node (ref "DS2") (pin "1") (pinfunction "A_1") (pintype "passive"))
      (node (ref "R11") (pin "1") (pinfunction "1_1") (pintype "passive"))
    )
    (net (code "76") (name "Net-(J1-Pad1)") (class "Default")
      (node (ref "J1") (pin "1") (pinfunction "1_1") (pintype "passive"))
      (node (ref "J1") (pin "2") (pinfunction "2_2") (pintype "passive"))
      (node (ref "W7") (pin "1") (pinfunction "1_1") (pintype "passive"))
      (node (ref "W8") (pin "1") (pinfunction "1_1") (pintype "passive"))
    )
    (net (code "77") (name "Net-(J1-Pad3)") (class "Default")
      (node (ref "J1") (pin "3") (pinfunction "3_3") (pintype "passive"))
      (node (ref "R2") (pin "2") (pinfunction "2_2") (pintype "passive"))
    )
    (net (code "78") (name "Net-(J1-Pad4)") (class "Default")
      (node (ref "J1") (pin "4") (pinfunction "4_4") (pintype "passive"))
      (node (ref "R4") (pin "2") (pinfunction "2_2") (pintype "passive"))
    )
    (net (code "79") (name "Net-(J7-Pad3)") (class "Default")
      (node (ref "J7") (pin "3") (pinfunction "3_3") (pintype "passive"))
      (node (ref "W10") (pin "1") (pinfunction "1_1") (pintype "passive"))
      (node (ref "W14") (pin "1") (pinfunction "1_1") (pintype "passive"))
    )
    (net (code "80") (name "Net-(J8-Pad3)") (class "Default")
      (node (ref "J8") (pin "3") (pinfunction "3_3") (pintype "passive"))
      (node (ref "W11") (pin "1") (pinfunction "1_1") (pintype "passive"))
      (node (ref "W15") (pin "1") (pinfunction "1_1") (pintype "passive"))
    )
    (net (code "81") (name "Net-(J9-Pad3)") (class "Default")
      (node (ref "J9") (pin "3") (pinfunction "3_3") (pintype "passive"))
      (node (ref "W12") (pin "1") (pinfunction "1_1") (pintype "passive"))
      (node (ref "W16") (pin "1") (pinfunction "1_1") (pintype "passive"))
    )
    (net (code "82") (name "Net-(U1-3V3)") (class "Default")
      (node (ref "C1") (pin "1") (pinfunction "1_1") (pintype "passive"))
      (node (ref "C2") (pin "1") (pinfunction "1_1") (pintype "passive"))
      (node (ref "P1") (pin "1") (pinfunction "1_1") (pintype "passive"))
      (node (ref "R6") (pin "2") (pinfunction "2_2") (pintype "passive"))
      (node (ref "S1") (pin "1") (pinfunction "1_1") (pintype "passive"))
      (node (ref "U1") (pin "2") (pinfunction "3V3_2") (pintype "bidirectional"))
    )
    (net (code "83") (name "Net-(U2-A0)") (class "Default")
      (node (ref "U2") (pin "1") (pinfunction "A0_1") (pintype "input"))
      (node (ref "W5") (pin "1") (pinfunction "1_1") (pintype "passive"))
      (node (ref "W6") (pin "2") (pinfunction "2_2") (pintype "passive"))
    )
    (net (code "84") (name "Net-(U2-A1)") (class "Default")
      (node (ref "U2") (pin "2") (pinfunction "A1_2") (pintype "input"))
      (node (ref "W3") (pin "1") (pinfunction "1_1") (pintype "passive"))
      (node (ref "W4") (pin "2") (pinfunction "2_2") (pintype "passive"))
    )
    (net (code "85") (name "Net-(U2-A2)") (class "Default")
      (node (ref "U2") (pin "3") (pinfunction "A2_3") (pintype "input"))
      (node (ref "W1") (pin "1") (pinfunction "1_1") (pintype "passive"))
      (node (ref "W2") (pin "2") (pinfunction "2_2") (pintype "passive"))
    )
    (net (code "86") (name "Net-(U2-~{INT})") (class "Default")
      (node (ref "R1") (pin "1") (pinfunction "1_1") (pintype "passive"))
      (node (ref "U2") (pin "13") (pinfunction "~{INT}_13") (pintype "open_collector"))
    )
    (net (code "87") (name "Net-(U7-Output)") (class "Default")
      (node (ref "U7") (pin "4") (pinfunction "Output_4") (pintype "output"))
      (node (ref "W17") (pin "2") (pinfunction "2_2") (pintype "passive"))
    )
    (net (code "88") (name "unconnected-(D1-C-Pad1)") (class "Default")
      (node (ref "D1") (pin "1") (pinfunction "C_1") (pintype "passive"))
    )
    (net (code "89") (name "unconnected-(U1-IO3-Pad15)") (class "Default")
      (node (ref "U1") (pin "15") (pinfunction "IO3_15") (pintype "bidirectional+no_connect"))
    )
    (net (code "90") (name "unconnected-(U3-ALERT{slash}RDY-Pad2)") (class "Default")
      (node (ref "U3") (pin "2") (pinfunction "ALERT/RDY_2") (pintype "open_collector+no_connect"))
    )
    (net (code "91") (name "unconnected-(U4-ALERT{slash}RDY-Pad2)") (class "Default")
      (node (ref "U4") (pin "2") (pinfunction "ALERT/RDY_2") (pintype "open_collector+no_connect"))
    )
    (net (code "92") (name "unconnected-(U6-A8-Pad9)") (class "Default")
      (node (ref "U6") (pin "9") (pinfunction "A8_9") (pintype "bidirectional"))
    )
    (net (code "93") (name "unconnected-(U6-B8-Pad12)") (class "Default")
      (node (ref "U6") (pin "12") (pinfunction "B8_12") (pintype "bidirectional"))
    )
  )
)
